# Power.net
KiCad netlist of a schematic drawn in EAGLE
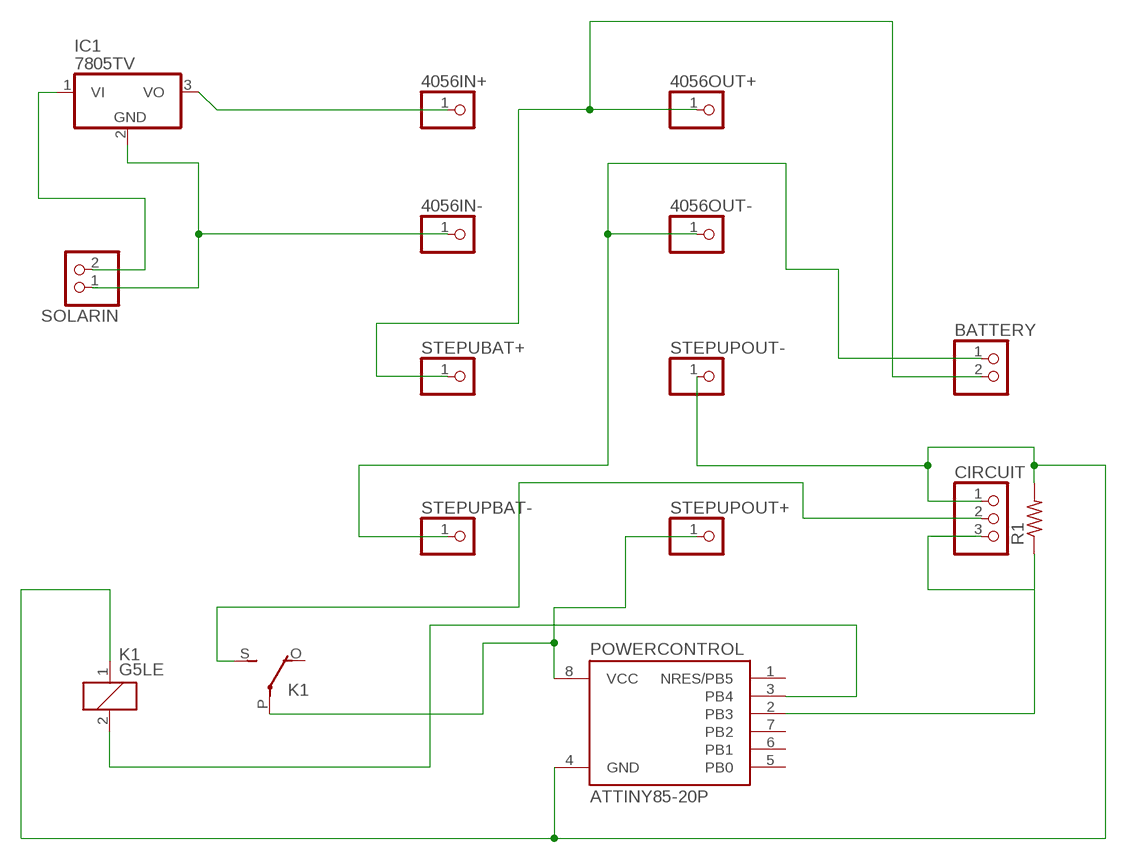
[diagram p0: schematic, sheet 1]

(export (version "E")
  (design (tool "Eeschema 10.0.6"))
  (components
    (comp (ref "4056IN+")
      (value "PINHD-1X1")
      (footprint "eagle-import:1X01")
      (libsource (lib "eagle-import") (part "PINHD-1X1"))
    )
    (comp (ref "4056IN-")
      (value "PINHD-1X1")
      (footprint "eagle-import:1X01")
      (libsource (lib "eagle-import") (part "PINHD-1X1"))
    )
    (comp (ref "4056OUT+")
      (value "PINHD-1X1")
      (footprint "eagle-import:1X01")
      (libsource (lib "eagle-import") (part "PINHD-1X1"))
    )
    (comp (ref "4056OUT-")
      (value "PINHD-1X1")
      (footprint "eagle-import:1X01")
      (libsource (lib "eagle-import") (part "PINHD-1X1"))
    )
    (comp (ref "BATTERY")
      (value "PINHD-1X2")
      (footprint "eagle-import:1X02")
      (libsource (lib "eagle-import") (part "PINHD-1X2"))
    )
    (comp (ref "CIRCUIT")
      (value "PINHD-1X3")
      (footprint "eagle-import:1X03")
      (libsource (lib "eagle-import") (part "PINHD-1X3"))
    )
    (comp (ref "IC1")
      (value "7805TV")
      (footprint "eagle-import:TO220V")
      (libsource (lib "eagle-import") (part "78TV05"))
    )
    (comp (ref "K1")
      (value "G5LE")
      (footprint "eagle-import:G5LE")
      (libsource (lib "eagle-import") (part "G5LE"))
    )
    (comp (ref "POWERCONTROL")
      (value "ATTINY85-20P")
      (footprint "eagle-import:PDIP08_300MIL")
      (libsource (lib "eagle-import") (part "ATTINY85P-20"))
    )
    (comp (ref "R1")
      (value "R-US_0204/7")
      (footprint "eagle-import:0204_7")
      (libsource (lib "eagle-import") (part "R-US_0204/7"))
    )
    (comp (ref "SOLARIN")
      (value "PINHD-1X2")
      (footprint "eagle-import:1X02")
      (libsource (lib "eagle-import") (part "PINHD-1X2"))
    )
    (comp (ref "STEPUBAT+")
      (value "PINHD-1X1")
      (footprint "eagle-import:1X01")
      (libsource (lib "eagle-import") (part "PINHD-1X1"))
    )
    (comp (ref "STEPUPBAT-")
      (value "PINHD-1X1")
      (footprint "eagle-import:1X01")
      (libsource (lib "eagle-import") (part "PINHD-1X1"))
    )
    (comp (ref "STEPUPOUT+")
      (value "PINHD-1X1")
      (footprint "eagle-import:1X01")
      (libsource (lib "eagle-import") (part "PINHD-1X1"))
    )
    (comp (ref "STEPUPOUT-")
      (value "PINHD-1X1")
      (footprint "eagle-import:1X01")
      (libsource (lib "eagle-import") (part "PINHD-1X1"))
    )
  )
  (nets
    (net (code "1") (name "Net-(4056OUT+-Pad1)") (class "Default")
      (node (ref "4056OUT+") (pin "1") (pinfunction "1_1") (pintype "passive"))
      (node (ref "BATTERY") (pin "2") (pinfunction "2_2") (pintype "passive"))
      (node (ref "STEPUBAT+") (pin "1") (pinfunction "1_1") (pintype "passive"))
    )
    (net (code "2") (name "Net-(4056OUT--Pad1)") (class "Default")
      (node (ref "4056OUT-") (pin "1") (pinfunction "1_1") (pintype "passive"))
      (node (ref "BATTERY") (pin "1") (pinfunction "1_1") (pintype "passive"))
      (node (ref "STEPUPBAT-") (pin "1") (pinfunction "1_1") (pintype "passive"))
    )
    (net (code "3") (name "Net-(CIRCUIT-Pad2)") (class "Default")
      (node (ref "CIRCUIT") (pin "2") (pinfunction "2_2") (pintype "passive"))
      (node (ref "K1") (pin "S") (pinfunction "S_S") (pintype "passive"))
    )
    (net (code "4") (name "Net-(IC1-GND)") (class "Default")
      (node (ref "4056IN-") (pin "1") (pinfunction "1_1") (pintype "passive"))
      (node (ref "IC1") (pin "2") (pinfunction "GND_2") (pintype "passive"))
      (node (ref "SOLARIN") (pin "1") (pinfunction "1_1") (pintype "passive"))
    )
    (net (code "5") (name "Net-(IC1-VI)") (class "Default")
      (node (ref "IC1") (pin "1") (pinfunction "VI_1") (pintype "input"))
      (node (ref "SOLARIN") (pin "2") (pinfunction "2_2") (pintype "passive"))
    )
    (net (code "6") (name "Net-(IC1-VO)") (class "Default")
      (node (ref "4056IN+") (pin "1") (pinfunction "1_1") (pintype "passive"))
      (node (ref "IC1") (pin "3") (pinfunction "VO_3") (pintype "passive"))
    )
    (net (code "7") (name "Net-(POWERCONTROL-GND)") (class "Default")
      (node (ref "CIRCUIT") (pin "1") (pinfunction "1_1") (pintype "passive"))
      (node (ref "K1") (pin "1") (pinfunction "1_1") (pintype "passive"))
      (node (ref "POWERCONTROL") (pin "4") (pinfunction "GND_4") (pintype "power_in"))
      (node (ref "R1") (pin "2") (pinfunction "2_2") (pintype "passive"))
      (node (ref "STEPUPOUT-") (pin "1") (pinfunction "1_1") (pintype "passive"))
    )
    (net (code "8") (name "Net-(POWERCONTROL-PB3)") (class "Default")
      (node (ref "CIRCUIT") (pin "3") (pinfunction "3_3") (pintype "passive"))
      (node (ref "POWERCONTROL") (pin "2") (pinfunction "PB3_2") (pintype "bidirectional"))
      (node (ref "R1") (pin "1") (pinfunction "1_1") (pintype "passive"))
    )
    (net (code "9") (name "Net-(POWERCONTROL-PB4)") (class "Default")
      (node (ref "K1") (pin "2") (pinfunction "2_2") (pintype "passive"))
      (node (ref "POWERCONTROL") (pin "3") (pinfunction "PB4_3") (pintype "bidirectional"))
    )
    (net (code "10") (name "Net-(POWERCONTROL-VCC)") (class "Default")
      (node (ref "K1") (pin "P") (pinfunction "P_P") (pintype "passive"))
      (node (ref "POWERCONTROL") (pin "8") (pinfunction "VCC_8") (pintype "power_in"))
      (node (ref "STEPUPOUT+") (pin "1") (pinfunction "1_1") (pintype "passive"))
    )
    (net (code "11") (name "unconnected-(K1-PadO)") (class "Default")
      (node (ref "K1") (pin "O") (pinfunction "O_O") (pintype "passive"))
    )
    (net (code "12") (name "unconnected-(POWERCONTROL-NRES{slash}PB5-Pad1)") (class "Default")
      (node (ref "POWERCONTROL") (pin "1") (pinfunction "NRES/PB5_1") (pintype "bidirectional"))
    )
    (net (code "13") (name "unconnected-(POWERCONTROL-PB0-Pad5)") (class "Default")
      (node (ref "POWERCONTROL") (pin "5") (pinfunction "PB0_5") (pintype "bidirectional"))
    )
    (net (code "14") (name "unconnected-(POWERCONTROL-PB1-Pad6)") (class "Default")
      (node (ref "POWERCONTROL") (pin "6") (pinfunction "PB1_6") (pintype "bidirectional"))
    )
    (net (code "15") (name "unconnected-(POWERCONTROL-PB2-Pad7)") (class "Default")
      (node (ref "POWERCONTROL") (pin "7") (pinfunction "PB2_7") (pintype "bidirectional"))
    )
  )
)
